# 2-MCU.net
KiCad netlist of a schematic drawn in Altium Designer
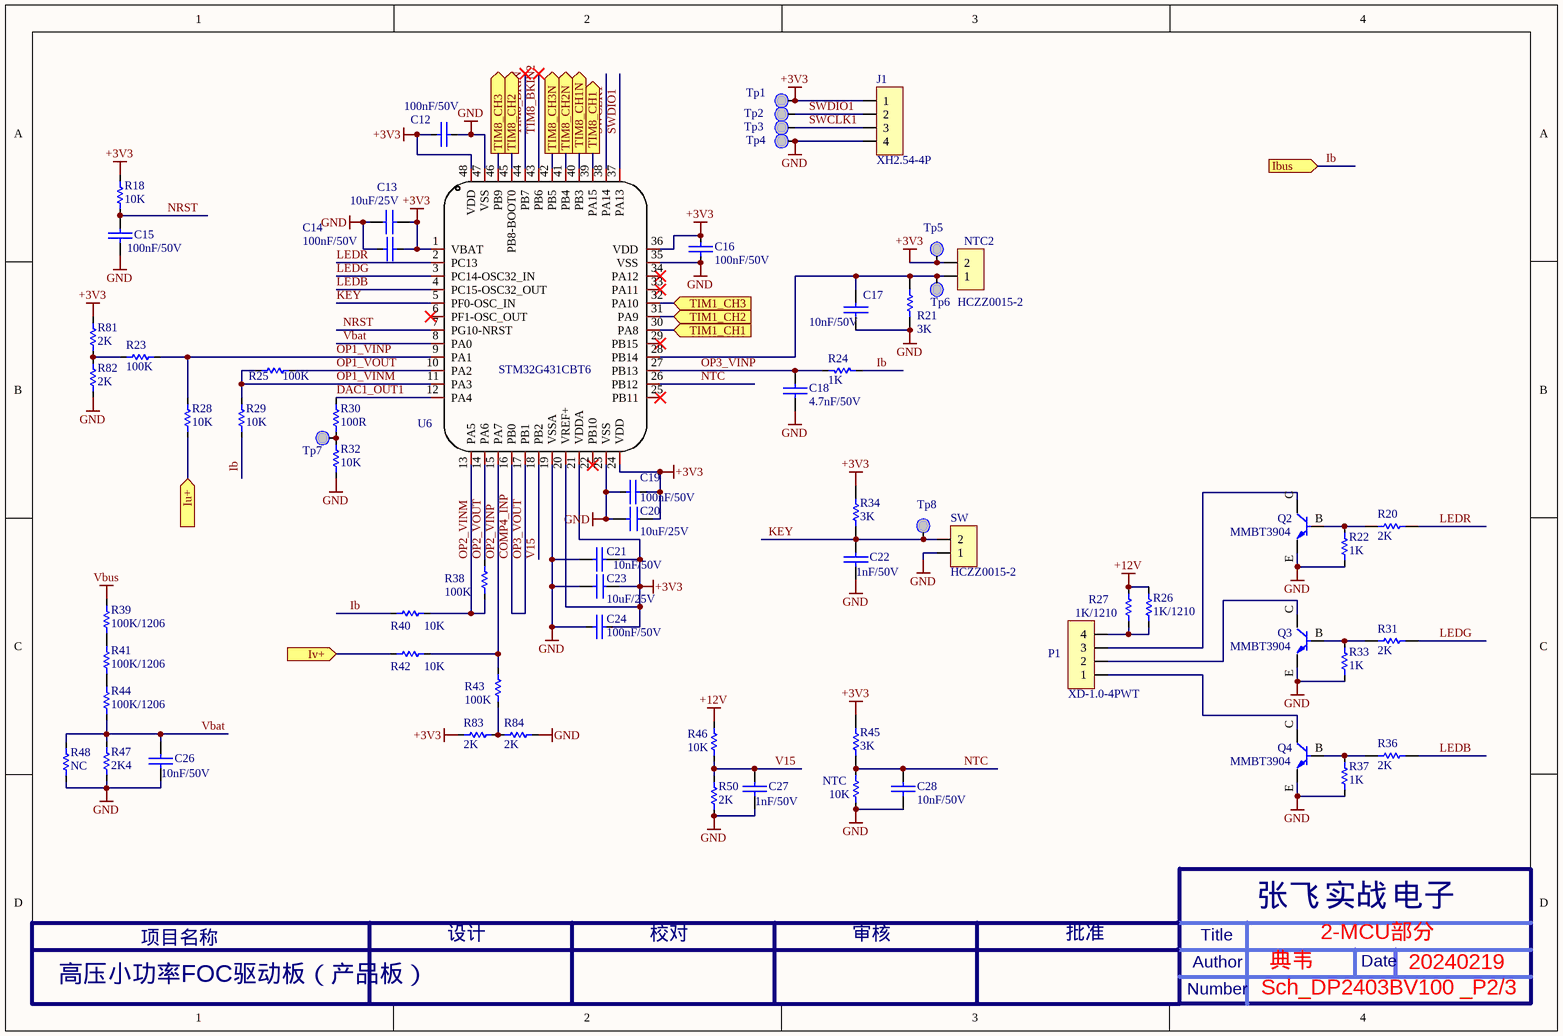
[diagram p0: 2-MCU部分.SchDoc]

(export (version "E")
  (design (tool "Eeschema 10.0.6"))
  (components
    (comp (ref "C12")
      (value "100nF/50V")
      (footprint "C0603")
      (description "贴片电容")
      (libsource (lib "*") (part "CAP NP"))
    )
    (comp (ref "C13")
      (value "10uF/25V")
      (footprint "C0805")
      (description "贴片电容")
      (fields
        (field (name "VOLTAGE") "<Voltage>")
        (field (name "MANUFACTURER") "TDK")
        (field (name "CREATED BY") "JJJ")
      )
      (libsource (lib "*") (part "CAP NP_0"))
    )
    (comp (ref "C14")
      (value "100nF/50V")
      (footprint "C0603")
      (description "贴片电容")
      (libsource (lib "*") (part "CAP NP"))
    )
    (comp (ref "C15")
      (value "100nF/50V")
      (footprint "C0603")
      (description "贴片电容")
      (libsource (lib "*") (part "CAP"))
    )
    (comp (ref "C16")
      (value "100nF/50V")
      (footprint "C0603")
      (description "贴片电容")
      (libsource (lib "*") (part "CAP NP"))
    )
    (comp (ref "C17")
      (value "10nF/50V")
      (footprint "C0603")
      (description "贴片电容")
      (libsource (lib "*") (part "CAP"))
    )
    (comp (ref "C18")
      (value "4.7nF/50V")
      (footprint "C0603")
      (description "贴片电容")
      (libsource (lib "*") (part "CAP"))
    )
    (comp (ref "C19")
      (value "100nF/50V")
      (footprint "C0603")
      (description "贴片电容")
      (libsource (lib "*") (part "CAP NP"))
    )
    (comp (ref "C20")
      (value "10uF/25V")
      (footprint "C0805")
      (description "贴片电容")
      (fields
        (field (name "VOLTAGE") "<Voltage>")
        (field (name "MANUFACTURER") "TDK")
        (field (name "CREATED BY") "JJJ")
      )
      (libsource (lib "*") (part "CAP NP_0"))
    )
    (comp (ref "C21")
      (value "10nF/50V")
      (footprint "C0603")
      (description "贴片电容")
      (libsource (lib "*") (part "CAP"))
    )
    (comp (ref "C22")
      (value "1nF/50V")
      (footprint "C0603")
      (description "贴片电容")
      (libsource (lib "*") (part "CAP"))
    )
    (comp (ref "C23")
      (value "10uF/25V")
      (footprint "C0805")
      (description "贴片电容")
      (fields
        (field (name "VOLTAGE") "<Voltage>")
        (field (name "MANUFACTURER") "TDK")
        (field (name "CREATED BY") "JJJ")
      )
      (libsource (lib "*") (part "CAP NP_0"))
    )
    (comp (ref "C24")
      (value "100nF/50V")
      (footprint "C0603")
      (description "贴片电容")
      (libsource (lib "*") (part "CAP NP"))
    )
    (comp (ref "C26")
      (value "10nF/50V")
      (footprint "C0603")
      (description "贴片电容")
      (libsource (lib "*") (part "CAP"))
    )
    (comp (ref "C27")
      (value "1nF/50V")
      (footprint "C0603")
      (description "贴片电容")
      (libsource (lib "*") (part "CAP"))
    )
    (comp (ref "C28")
      (value "10nF/50V")
      (footprint "C0603")
      (description "贴片电容")
      (libsource (lib "*") (part "CAP"))
    )
    (comp (ref "J1")
      (value "XH2.54-4P")
      (footprint "SIP4")
      (description "接插件")
      (libsource (lib "ZF_SchLib_V0.15") (part "4PIN"))
    )
    (comp (ref "NTC")
      (value "10K")
      (footprint "R0603")
      (description "NTC=10K")
      (fields
        (field (name "MANUFACTURER") "Generic Components")
        (field (name "PUBLISHER") "Altium Hobart Technology Centre")
      )
      (libsource (lib "ZF-V1.00(2022-6-13)") (part "Res"))
    )
    (comp (ref "NTC2")
      (value "HCZZ0015-2")
      (footprint "PIN-2-LS")
      (description "HCZZ0015-2,2P,1.25mm")
      (libsource (lib "ZF-V1.00(2022-6-13)") (part "2PIN"))
    )
    (comp (ref "P1")
      (value "XD-1.0-4PWT")
      (footprint "PIN-4-WS")
      (description "XD-1.0-4PWT,1*4P")
      (libsource (lib "") (part "4PIN_1"))
    )
    (comp (ref "Q2")
      (value "MMBT3904")
      (footprint "SOT-23-BCE")
      (description "三极管")
      (libsource (lib "ZF_SchLib_V0.15") (part "BJT-NPN"))
    )
    (comp (ref "Q3")
      (value "MMBT3904")
      (footprint "SOT-23-BCE")
      (description "三极管")
      (libsource (lib "ZF_SchLib_V0.15") (part "BJT-NPN"))
    )
    (comp (ref "Q4")
      (value "MMBT3904")
      (footprint "SOT-23-BCE")
      (description "三极管")
      (libsource (lib "ZF_SchLib_V0.15") (part "BJT-NPN"))
    )
    (comp (ref "R18")
      (value "10K")
      (footprint "R0603")
      (description "电阻")
      (fields
        (field (name "MANUFACTURER") "Generic Components")
        (field (name "PUBLISHER") "Altium Hobart Technology Centre")
      )
      (libsource (lib "ZF-V1.00(2022-6-13)") (part "Res"))
    )
    (comp (ref "R20")
      (value "2K")
      (footprint "R0603")
      (description "电阻")
      (fields
        (field (name "MANUFACTURER") "Generic Components")
        (field (name "PUBLISHER") "Altium Hobart Technology Centre")
      )
      (libsource (lib "ZF_SchLib_V0.15") (part "Res"))
    )
    (comp (ref "R21")
      (value "3K")
      (footprint "R0603")
      (description "电阻")
      (fields
        (field (name "MANUFACTURER") "Generic Components")
        (field (name "PUBLISHER") "Altium Hobart Technology Centre")
      )
      (libsource (lib "ZF_SchLib_V0.15") (part "Res"))
    )
    (comp (ref "R22")
      (value "1K")
      (footprint "R0603")
      (description "电阻")
      (fields
        (field (name "MANUFACTURER") "Generic Components")
        (field (name "PUBLISHER") "Altium Hobart Technology Centre")
      )
      (libsource (lib "ZF-V1.00(2022-6-13)") (part "Res"))
    )
    (comp (ref "R23")
      (value "100K")
      (footprint "R0603")
      (description "电阻")
      (fields
        (field (name "MANUFACTURER") "Generic Components")
        (field (name "PUBLISHER") "Altium Hobart Technology Centre")
      )
      (libsource (lib "ZF-V1.00(2022-6-13)") (part "Res"))
    )
    (comp (ref "R24")
      (value "1K")
      (footprint "R0603")
      (description "电阻")
      (fields
        (field (name "MANUFACTURER") "Generic Components")
        (field (name "PUBLISHER") "Altium Hobart Technology Centre")
      )
      (libsource (lib "ZF-V1.00(2022-6-13)") (part "Res"))
    )
    (comp (ref "R25")
      (value "100K")
      (footprint "R0603")
      (description "电阻")
      (fields
        (field (name "MANUFACTURER") "Generic Components")
        (field (name "PUBLISHER") "Altium Hobart Technology Centre")
      )
      (libsource (lib "ZF-V1.00(2022-6-13)") (part "Res"))
    )
    (comp (ref "R26")
      (value "1K/1210")
      (footprint "R1210")
      (description "电阻")
      (fields
        (field (name "MANUFACTURER") "Generic Components")
        (field (name "PUBLISHER") "Altium Hobart Technology Centre")
      )
      (libsource (lib "ZF-V1.00(2022-6-13)") (part "Res"))
    )
    (comp (ref "R27")
      (value "1K/1210")
      (footprint "R1210")
      (description "电阻")
      (fields
        (field (name "MANUFACTURER") "Generic Components")
        (field (name "PUBLISHER") "Altium Hobart Technology Centre")
      )
      (libsource (lib "ZF-V1.00(2022-6-13)") (part "Res"))
    )
    (comp (ref "R28")
      (value "10K")
      (footprint "R0603")
      (description "电阻")
      (fields
        (field (name "MANUFACTURER") "Generic Components")
        (field (name "PUBLISHER") "Altium Hobart Technology Centre")
      )
      (libsource (lib "ZF-V1.00(2022-6-13)") (part "Res"))
    )
    (comp (ref "R29")
      (value "10K")
      (footprint "R0603")
      (description "电阻")
      (fields
        (field (name "MANUFACTURER") "Generic Components")
        (field (name "PUBLISHER") "Altium Hobart Technology Centre")
      )
      (libsource (lib "ZF-V1.00(2022-6-13)") (part "Res"))
    )
    (comp (ref "R30")
      (value "100R")
      (footprint "R0603")
      (description "电阻")
      (fields
        (field (name "MANUFACTURER") "Generic Components")
        (field (name "PUBLISHER") "Altium Hobart Technology Centre")
      )
      (libsource (lib "ZF-V1.00(2022-6-13)") (part "Res"))
    )
    (comp (ref "R31")
      (value "2K")
      (footprint "R0603")
      (description "电阻")
      (fields
        (field (name "MANUFACTURER") "Generic Components")
        (field (name "PUBLISHER") "Altium Hobart Technology Centre")
      )
      (libsource (lib "ZF_SchLib_V0.15") (part "Res"))
    )
    (comp (ref "R32")
      (value "10K")
      (footprint "R0603")
      (description "电阻")
      (fields
        (field (name "MANUFACTURER") "Generic Components")
        (field (name "PUBLISHER") "Altium Hobart Technology Centre")
      )
      (libsource (lib "ZF-V1.00(2022-6-13)") (part "Res"))
    )
    (comp (ref "R33")
      (value "1K")
      (footprint "R0603")
      (description "电阻")
      (fields
        (field (name "MANUFACTURER") "Generic Components")
        (field (name "PUBLISHER") "Altium Hobart Technology Centre")
      )
      (libsource (lib "ZF-V1.00(2022-6-13)") (part "Res"))
    )
    (comp (ref "R34")
      (value "3K")
      (footprint "R0603")
      (description "电阻")
      (fields
        (field (name "MANUFACTURER") "Generic Components")
        (field (name "PUBLISHER") "Altium Hobart Technology Centre")
      )
      (libsource (lib "ZF_SchLib_V0.15") (part "Res"))
    )
    (comp (ref "R36")
      (value "2K")
      (footprint "R0603")
      (description "电阻")
      (fields
        (field (name "MANUFACTURER") "Generic Components")
        (field (name "PUBLISHER") "Altium Hobart Technology Centre")
      )
      (libsource (lib "ZF_SchLib_V0.15") (part "Res"))
    )
    (comp (ref "R37")
      (value "1K")
      (footprint "R0603")
      (description "电阻")
      (fields
        (field (name "MANUFACTURER") "Generic Components")
        (field (name "PUBLISHER") "Altium Hobart Technology Centre")
      )
      (libsource (lib "ZF-V1.00(2022-6-13)") (part "Res"))
    )
    (comp (ref "R38")
      (value "100K")
      (footprint "R0603")
      (description "电阻")
      (fields
        (field (name "MANUFACTURER") "Generic Components")
        (field (name "PUBLISHER") "Altium Hobart Technology Centre")
      )
      (libsource (lib "ZF-V1.00(2022-6-13)") (part "Res"))
    )
    (comp (ref "R39")
      (value "100K/1206")
      (footprint "R1206")
      (description "电阻")
      (fields
        (field (name "MANUFACTURER") "Generic Components")
        (field (name "PUBLISHER") "Altium Hobart Technology Centre")
      )
      (libsource (lib "ZF-V1.00(2022-6-13)") (part "Res"))
    )
    (comp (ref "R40")
      (value "10K")
      (footprint "R0603")
      (description "电阻")
      (fields
        (field (name "MANUFACTURER") "Generic Components")
        (field (name "PUBLISHER") "Altium Hobart Technology Centre")
      )
      (libsource (lib "ZF-V1.00(2022-6-13)") (part "Res"))
    )
    (comp (ref "R41")
      (value "100K/1206")
      (footprint "R1206")
      (description "电阻")
      (fields
        (field (name "MANUFACTURER") "Generic Components")
        (field (name "PUBLISHER") "Altium Hobart Technology Centre")
      )
      (libsource (lib "ZF-V1.00(2022-6-13)") (part "Res"))
    )
    (comp (ref "R42")
      (value "10K")
      (footprint "R0603")
      (description "电阻")
      (fields
        (field (name "MANUFACTURER") "Generic Components")
        (field (name "PUBLISHER") "Altium Hobart Technology Centre")
      )
      (libsource (lib "ZF-V1.00(2022-6-13)") (part "Res"))
    )
    (comp (ref "R43")
      (value "100K")
      (footprint "R0603")
      (description "电阻")
      (fields
        (field (name "MANUFACTURER") "Generic Components")
        (field (name "PUBLISHER") "Altium Hobart Technology Centre")
      )
      (libsource (lib "ZF-V1.00(2022-6-13)") (part "Res"))
    )
    (comp (ref "R44")
      (value "100K/1206")
      (footprint "R1206")
      (description "电阻")
      (fields
        (field (name "MANUFACTURER") "Generic Components")
        (field (name "PUBLISHER") "Altium Hobart Technology Centre")
      )
      (libsource (lib "ZF-V1.00(2022-6-13)") (part "Res"))
    )
    (comp (ref "R45")
      (value "3K")
      (footprint "R0603")
      (description "电阻")
      (fields
        (field (name "MANUFACTURER") "Generic Components")
        (field (name "PUBLISHER") "Altium Hobart Technology Centre")
      )
      (libsource (lib "ZF_SchLib_V0.15") (part "Res"))
    )
    (comp (ref "R46")
      (value "10K")
      (footprint "R0603")
      (description "电阻")
      (fields
        (field (name "MANUFACTURER") "Generic Components")
        (field (name "PUBLISHER") "Altium Hobart Technology Centre")
      )
      (libsource (lib "ZF-V1.00(2022-6-13)") (part "Res"))
    )
    (comp (ref "R47")
      (value "2K4")
      (footprint "R0603")
      (description "电阻")
      (fields
        (field (name "MANUFACTURER") "Generic Components")
        (field (name "PUBLISHER") "Altium Hobart Technology Centre")
      )
      (libsource (lib "ZF-V1.00(2022-6-13)") (part "Res"))
    )
    (comp (ref "R48")
      (value "NC")
      (footprint "R0603")
      (description "电阻")
      (fields
        (field (name "MANUFACTURER") "Generic Components")
        (field (name "PUBLISHER") "Altium Hobart Technology Centre")
      )
      (libsource (lib "ZF-V1.00(2022-6-13)") (part "Res"))
    )
    (comp (ref "R50")
      (value "2K")
      (footprint "R0603")
      (description "电阻")
      (fields
        (field (name "MANUFACTURER") "Generic Components")
        (field (name "PUBLISHER") "Altium Hobart Technology Centre")
      )
      (libsource (lib "ZF-V1.00(2022-6-13)") (part "Res"))
    )
    (comp (ref "R81")
      (value "2K")
      (footprint "R0603")
      (description "电阻")
      (fields
        (field (name "MANUFACTURER") "Generic Components")
        (field (name "PUBLISHER") "Altium Hobart Technology Centre")
      )
      (libsource (lib "ZF-V1.00(2022-6-13)") (part "Res"))
    )
    (comp (ref "R82")
      (value "2K")
      (footprint "R0603")
      (description "电阻")
      (fields
        (field (name "MANUFACTURER") "Generic Components")
        (field (name "PUBLISHER") "Altium Hobart Technology Centre")
      )
      (libsource (lib "ZF-V1.00(2022-6-13)") (part "Res"))
    )
    (comp (ref "R83")
      (value "2K")
      (footprint "R0603")
      (description "电阻")
      (fields
        (field (name "MANUFACTURER") "Generic Components")
        (field (name "PUBLISHER") "Altium Hobart Technology Centre")
      )
      (libsource (lib "ZF-V1.00(2022-6-13)") (part "Res"))
    )
    (comp (ref "R84")
      (value "2K")
      (footprint "R0603")
      (description "电阻")
      (fields
        (field (name "MANUFACTURER") "Generic Components")
        (field (name "PUBLISHER") "Altium Hobart Technology Centre")
      )
      (libsource (lib "ZF-V1.00(2022-6-13)") (part "Res"))
    )
    (comp (ref "SW")
      (value "HCZZ0015-2")
      (footprint "PIN-2-LS")
      (description "HCZZ0015-2,2P,1.25mm")
      (libsource (lib "ZF-V1.00(2022-6-13)") (part "2PIN"))
    )
    (comp (ref "Tp1")
      (value "test point")
      (footprint "Test_Port")
      (libsource (lib "RUKING-Passive Component Schematic library V01") (part "test point"))
    )
    (comp (ref "Tp2")
      (value "test point")
      (footprint "Test_Port")
      (libsource (lib "RUKING-Passive Component Schematic library V01") (part "test point"))
    )
    (comp (ref "Tp3")
      (value "test point")
      (footprint "Test_Port")
      (libsource (lib "RUKING-Passive Component Schematic library V01") (part "test point"))
    )
    (comp (ref "Tp4")
      (value "test point")
      (footprint "Test_Port")
      (libsource (lib "RUKING-Passive Component Schematic library V01") (part "test point"))
    )
    (comp (ref "Tp5") (value "test point") (footprint "Test_Port") (libsource (lib "") (part "test point_1")))
    (comp (ref "Tp6") (value "test point") (footprint "Test_Port") (libsource (lib "") (part "test point_2")))
    (comp (ref "Tp7")
      (value "test point")
      (footprint "Test_Port")
      (libsource (lib "RUKING-Passive Component Schematic library V01") (part "test point"))
    )
    (comp (ref "Tp8") (value "test point") (footprint "Test_Port") (libsource (lib "") (part "test point_1")))
    (comp (ref "U6")
      (value "STM32G431CBT6")
      (footprint "LQFP-48")
      (fields (field (name "MANUFACTURER") "ST(意法半导体)"))
      (libsource (lib "altium-import") (part "root_0_STM32G431CBT6_"))
    )
  )
  (nets
    (net (code "1") (name "+3V3") (class "Default")
      (node (ref "C12") (pin "2") (pinfunction "2_2") (pintype "passive"))
      (node (ref "C13") (pin "2") (pinfunction "2_2") (pintype "passive"))
      (node (ref "C14") (pin "1") (pinfunction "1_1") (pintype "passive"))
      (node (ref "C16") (pin "2") (pinfunction "2_2") (pintype "passive"))
      (node (ref "C19") (pin "2") (pinfunction "2_2") (pintype "passive"))
      (node (ref "C20") (pin "1") (pinfunction "1_1") (pintype "passive"))
      (node (ref "C21") (pin "2") (pinfunction "2_2") (pintype "passive"))
      (node (ref "C23") (pin "1") (pinfunction "1_1") (pintype "passive"))
      (node (ref "C24") (pin "2") (pinfunction "2_2") (pintype "passive"))
      (node (ref "J1") (pin "1") (pinfunction "1_1") (pintype "passive"))
      (node (ref "NTC2") (pin "2") (pinfunction "2_2") (pintype "passive"))
      (node (ref "R18") (pin "1") (pinfunction "1_1") (pintype "passive"))
      (node (ref "R34") (pin "1") (pinfunction "1_1") (pintype "passive"))
      (node (ref "R45") (pin "1") (pinfunction "1_1") (pintype "passive"))
      (node (ref "R81") (pin "1") (pinfunction "1_1") (pintype "passive"))
      (node (ref "R83") (pin "1") (pinfunction "1_1") (pintype "passive"))
      (node (ref "Tp1") (pin "1") (pinfunction "Test_1") (pintype "passive"))
      (node (ref "Tp5") (pin "1") (pinfunction "Test_1") (pintype "passive"))
      (node (ref "U6") (pin "1") (pinfunction "VBAT_1") (pintype "passive"))
      (node (ref "U6") (pin "20") (pinfunction "VREF+_20") (pintype "passive"))
      (node (ref "U6") (pin "21") (pinfunction "VDDA_21") (pintype "passive"))
      (node (ref "U6") (pin "24") (pinfunction "VDD_24") (pintype "passive"))
      (node (ref "U6") (pin "36") (pinfunction "VDD_36") (pintype "passive"))
      (node (ref "U6") (pin "48") (pinfunction "VDD_48") (pintype "passive"))
    )
    (net (code "2") (name "+12V") (class "Default")
      (node (ref "R26") (pin "1") (pinfunction "1_1") (pintype "passive"))
      (node (ref "R27") (pin "1") (pinfunction "1_1") (pintype "passive"))
      (node (ref "R46") (pin "1") (pinfunction "1_1") (pintype "passive"))
    )
    (net (code "3") (name "/COMP4_INP") (class "Default")
      (node (ref "U6") (pin "16") (pinfunction "PB0_16") (pintype "passive"))
      (node (ref "U6") (pin "17") (pinfunction "PB1_17") (pintype "passive"))
    )
    (net (code "4") (name "/DAC1_OUT1") (class "Default")
      (node (ref "R30") (pin "1") (pinfunction "1_1") (pintype "passive"))
      (node (ref "U6") (pin "12") (pinfunction "PA4_12") (pintype "passive"))
    )
    (net (code "5") (name "/Ib") (class "Default")
      (node (ref "R24") (pin "2") (pinfunction "2_2") (pintype "passive"))
      (node (ref "R29") (pin "1") (pinfunction "1_1") (pintype "passive"))
      (node (ref "R40") (pin "2") (pinfunction "2_2") (pintype "passive"))
    )
    (net (code "6") (name "/Iu+") (class "Default")
      (node (ref "R28") (pin "2") (pinfunction "2_2") (pintype "passive"))
    )
    (net (code "7") (name "/Iv+") (class "Default")
      (node (ref "R42") (pin "1") (pinfunction "1_1") (pintype "passive"))
    )
    (net (code "8") (name "/KEY") (class "Default")
      (node (ref "C22") (pin "1") (pinfunction "1_1") (pintype "passive"))
      (node (ref "R34") (pin "2") (pinfunction "2_2") (pintype "passive"))
      (node (ref "SW") (pin "2") (pinfunction "2_2") (pintype "passive"))
      (node (ref "Tp8") (pin "1") (pinfunction "Test_1") (pintype "passive"))
      (node (ref "U6") (pin "5") (pinfunction "PF0-OSC_IN_5") (pintype "passive"))
    )
    (net (code "9") (name "/LEDB") (class "Default")
      (node (ref "R36") (pin "2") (pinfunction "2_2") (pintype "passive"))
      (node (ref "U6") (pin "4") (pinfunction "PC15-OSC32_OUT_4") (pintype "passive"))
    )
    (net (code "10") (name "/LEDG") (class "Default")
      (node (ref "R31") (pin "2") (pinfunction "2_2") (pintype "passive"))
      (node (ref "U6") (pin "3") (pinfunction "PC14-OSC32_IN_3") (pintype "passive"))
    )
    (net (code "11") (name "/LEDR") (class "Default")
      (node (ref "R20") (pin "2") (pinfunction "2_2") (pintype "passive"))
      (node (ref "U6") (pin "2") (pinfunction "PC13_2") (pintype "passive"))
    )
    (net (code "12") (name "/NRST") (class "Default")
      (node (ref "C15") (pin "1") (pinfunction "1_1") (pintype "passive"))
      (node (ref "R18") (pin "2") (pinfunction "2_2") (pintype "passive"))
      (node (ref "U6") (pin "7") (pinfunction "PG10-NRST_7") (pintype "passive"))
    )
    (net (code "13") (name "/NTC") (class "Default")
      (node (ref "C28") (pin "2") (pinfunction "2_2") (pintype "passive"))
      (node (ref "NTC") (pin "1") (pinfunction "1_1") (pintype "passive"))
      (node (ref "R45") (pin "2") (pinfunction "2_2") (pintype "passive"))
      (node (ref "U6") (pin "26") (pinfunction "PB12_26") (pintype "passive"))
    )
    (net (code "14") (name "/OP1_VINM") (class "Default")
      (node (ref "R25") (pin "1") (pinfunction "1_1") (pintype "passive"))
      (node (ref "R29") (pin "2") (pinfunction "2_2") (pintype "passive"))
      (node (ref "U6") (pin "11") (pinfunction "PA3_11") (pintype "passive"))
    )
    (net (code "15") (name "/OP1_VINP") (class "Default")
      (node (ref "R23") (pin "1") (pinfunction "1_1") (pintype "passive"))
      (node (ref "R28") (pin "1") (pinfunction "1_1") (pintype "passive"))
      (node (ref "U6") (pin "9") (pinfunction "PA1_9") (pintype "passive"))
    )
    (net (code "16") (name "/OP1_VOUT") (class "Default")
      (node (ref "R25") (pin "2") (pinfunction "2_2") (pintype "passive"))
      (node (ref "U6") (pin "10") (pinfunction "PA2_10") (pintype "passive"))
    )
    (net (code "17") (name "/OP2_VINM") (class "Default")
      (node (ref "R38") (pin "1") (pinfunction "1_1") (pintype "passive"))
      (node (ref "R40") (pin "1") (pinfunction "1_1") (pintype "passive"))
      (node (ref "U6") (pin "13") (pinfunction "PA5_13") (pintype "passive"))
    )
    (net (code "18") (name "/OP2_VINP") (class "Default")
      (node (ref "R42") (pin "2") (pinfunction "2_2") (pintype "passive"))
      (node (ref "R43") (pin "1") (pinfunction "1_1") (pintype "passive"))
      (node (ref "U6") (pin "15") (pinfunction "PA7_15") (pintype "passive"))
    )
    (net (code "19") (name "/OP2_VOUT") (class "Default")
      (node (ref "R38") (pin "2") (pinfunction "2_2") (pintype "passive"))
      (node (ref "U6") (pin "14") (pinfunction "PA6_14") (pintype "passive"))
    )
    (net (code "20") (name "/OP3_VINP") (class "Default")
      (node (ref "C18") (pin "1") (pinfunction "1_1") (pintype "passive"))
      (node (ref "R24") (pin "1") (pinfunction "1_1") (pintype "passive"))
      (node (ref "U6") (pin "27") (pinfunction "PB13_27") (pintype "passive"))
    )
    (net (code "21") (name "/SWCLK1") (class "Default")
      (node (ref "J1") (pin "3") (pinfunction "3_3") (pintype "passive"))
      (node (ref "Tp3") (pin "1") (pinfunction "Test_1") (pintype "passive"))
      (node (ref "U6") (pin "38") (pinfunction "PA14_38") (pintype "passive"))
    )
    (net (code "22") (name "/SWDIO1") (class "Default")
      (node (ref "J1") (pin "2") (pinfunction "2_2") (pintype "passive"))
      (node (ref "Tp2") (pin "1") (pinfunction "Test_1") (pintype "passive"))
      (node (ref "U6") (pin "37") (pinfunction "PA13_37") (pintype "passive"))
    )
    (net (code "23") (name "/TIM1_CH1") (class "Default")
      (node (ref "U6") (pin "30") (pinfunction "PA8_30") (pintype "passive"))
    )
    (net (code "24") (name "/TIM1_CH2") (class "Default")
      (node (ref "U6") (pin "31") (pinfunction "PA9_31") (pintype "passive"))
    )
    (net (code "25") (name "/TIM1_CH3") (class "Default")
      (node (ref "U6") (pin "32") (pinfunction "PA10_32") (pintype "passive"))
    )
    (net (code "26") (name "/TIM8_BKIN") (class "Default")
      (node (ref "U6") (pin "44") (pinfunction "PB7_44") (pintype "passive+no_connect"))
    )
    (net (code "27") (name "/TIM8_BKIN2") (class "Default")
      (node (ref "U6") (pin "43") (pinfunction "PB6_43") (pintype "passive+no_connect"))
    )
    (net (code "28") (name "/TIM8_CH1") (class "Default")
      (node (ref "U6") (pin "39") (pinfunction "PA15_39") (pintype "passive"))
    )
    (net (code "29") (name "/TIM8_CH1N") (class "Default")
      (node (ref "U6") (pin "40") (pinfunction "PB3_40") (pintype "passive"))
    )
    (net (code "30") (name "/TIM8_CH2") (class "Default")
      (node (ref "U6") (pin "45") (pinfunction "PB8-BOOT0_45") (pintype "passive"))
    )
    (net (code "31") (name "/TIM8_CH2N") (class "Default")
      (node (ref "U6") (pin "41") (pinfunction "PB4_41") (pintype "passive"))
    )
    (net (code "32") (name "/TIM8_CH3") (class "Default")
      (node (ref "U6") (pin "46") (pinfunction "PB9_46") (pintype "passive"))
    )
    (net (code "33") (name "/TIM8_CH3N") (class "Default")
      (node (ref "U6") (pin "42") (pinfunction "PB5_42") (pintype "passive"))
    )
    (net (code "34") (name "/V15") (class "Default")
      (node (ref "C27") (pin "1") (pinfunction "1_1") (pintype "passive"))
      (node (ref "R46") (pin "2") (pinfunction "2_2") (pintype "passive"))
      (node (ref "R50") (pin "2") (pinfunction "2_2") (pintype "passive"))
      (node (ref "U6") (pin "18") (pinfunction "PB2_18") (pintype "passive"))
    )
    (net (code "35") (name "/Vbat") (class "Default")
      (node (ref "C26") (pin "1") (pinfunction "1_1") (pintype "passive"))
      (node (ref "R44") (pin "2") (pinfunction "2_2") (pintype "passive"))
      (node (ref "R47") (pin "2") (pinfunction "2_2") (pintype "passive"))
      (node (ref "R48") (pin "2") (pinfunction "2_2") (pintype "passive"))
      (node (ref "U6") (pin "8") (pinfunction "PA0_8") (pintype "passive"))
    )
    (net (code "36") (name "GND") (class "Default")
      (node (ref "C12") (pin "1") (pinfunction "1_1") (pintype "passive"))
      (node (ref "C13") (pin "1") (pinfunction "1_1") (pintype "passive"))
      (node (ref "C14") (pin "2") (pinfunction "2_2") (pintype "passive"))
      (node (ref "C15") (pin "2") (pinfunction "2_2") (pintype "passive"))
      (node (ref "C16") (pin "1") (pinfunction "1_1") (pintype "passive"))
      (node (ref "C17") (pin "1") (pinfunction "1_1") (pintype "passive"))
      (node (ref "C18") (pin "2") (pinfunction "2_2") (pintype "passive"))
      (node (ref "C19") (pin "1") (pinfunction "1_1") (pintype "passive"))
      (node (ref "C20") (pin "2") (pinfunction "2_2") (pintype "passive"))
      (node (ref "C21") (pin "1") (pinfunction "1_1") (pintype "passive"))
      (node (ref "C22") (pin "2") (pinfunction "2_2") (pintype "passive"))
      (node (ref "C23") (pin "2") (pinfunction "2_2") (pintype "passive"))
      (node (ref "C24") (pin "1") (pinfunction "1_1") (pintype "passive"))
      (node (ref "C26") (pin "2") (pinfunction "2_2") (pintype "passive"))
      (node (ref "C27") (pin "2") (pinfunction "2_2") (pintype "passive"))
      (node (ref "C28") (pin "1") (pinfunction "1_1") (pintype "passive"))
      (node (ref "J1") (pin "4") (pinfunction "4_4") (pintype "passive"))
      (node (ref "NTC") (pin "2") (pinfunction "2_2") (pintype "passive"))
      (node (ref "Q2") (pin "E") (pinfunction "2_E") (pintype "passive"))
      (node (ref "Q3") (pin "E") (pinfunction "2_E") (pintype "passive"))
      (node (ref "Q4") (pin "E") (pinfunction "2_E") (pintype "passive"))
      (node (ref "R21") (pin "2") (pinfunction "2_2") (pintype "passive"))
      (node (ref "R22") (pin "2") (pinfunction "2_2") (pintype "passive"))
      (node (ref "R32") (pin "1") (pinfunction "1_1") (pintype "passive"))
      (node (ref "R33") (pin "2") (pinfunction "2_2") (pintype "passive"))
      (node (ref "R37") (pin "2") (pinfunction "2_2") (pintype "passive"))
      (node (ref "R47") (pin "1") (pinfunction "1_1") (pintype "passive"))
      (node (ref "R48") (pin "1") (pinfunction "1_1") (pintype "passive"))
      (node (ref "R50") (pin "1") (pinfunction "1_1") (pintype "passive"))
      (node (ref "R82") (pin "2") (pinfunction "2_2") (pintype "passive"))
      (node (ref "R84") (pin "2") (pinfunction "2_2") (pintype "passive"))
      (node (ref "SW") (pin "1") (pinfunction "1_1") (pintype "passive"))
      (node (ref "Tp4") (pin "1") (pinfunction "Test_1") (pintype "passive"))
      (node (ref "U6") (pin "19") (pinfunction "VSSA_19") (pintype "passive"))
      (node (ref "U6") (pin "23") (pinfunction "VSS_23") (pintype "passive"))
      (node (ref "U6") (pin "35") (pinfunction "VSS_35") (pintype "passive"))
      (node (ref "U6") (pin "47") (pinfunction "VSS_47") (pintype "passive"))
    )
    (net (code "37") (name "Net-(P1-Pad4)") (class "Default")
      (node (ref "P1") (pin "4") (pinfunction "4_4") (pintype "passive"))
      (node (ref "R26") (pin "2") (pinfunction "2_2") (pintype "passive"))
      (node (ref "R27") (pin "2") (pinfunction "2_2") (pintype "passive"))
    )
    (net (code "38") (name "Net-(Q2-1)") (class "Default")
      (node (ref "Q2") (pin "B") (pinfunction "1_B") (pintype "passive"))
      (node (ref "R20") (pin "1") (pinfunction "1_1") (pintype "passive"))
      (node (ref "R22") (pin "1") (pinfunction "1_1") (pintype "passive"))
    )
    (net (code "39") (name "Net-(Q2-3)") (class "Default")
      (node (ref "P1") (pin "3") (pinfunction "3_3") (pintype "passive"))
      (node (ref "Q2") (pin "C") (pinfunction "3_C") (pintype "passive"))
    )
    (net (code "40") (name "Net-(Q3-1)") (class "Default")
      (node (ref "Q3") (pin "B") (pinfunction "1_B") (pintype "passive"))
      (node (ref "R31") (pin "1") (pinfunction "1_1") (pintype "passive"))
      (node (ref "R33") (pin "1") (pinfunction "1_1") (pintype "passive"))
    )
    (net (code "41") (name "Net-(Q3-3)") (class "Default")
      (node (ref "P1") (pin "2") (pinfunction "2_2") (pintype "passive"))
      (node (ref "Q3") (pin "C") (pinfunction "3_C") (pintype "passive"))
    )
    (net (code "42") (name "Net-(Q4-1)") (class "Default")
      (node (ref "Q4") (pin "B") (pinfunction "1_B") (pintype "passive"))
      (node (ref "R36") (pin "1") (pinfunction "1_1") (pintype "passive"))
      (node (ref "R37") (pin "1") (pinfunction "1_1") (pintype "passive"))
    )
    (net (code "43") (name "Net-(Q4-3)") (class "Default")
      (node (ref "P1") (pin "1") (pinfunction "1_1") (pintype "passive"))
      (node (ref "Q4") (pin "C") (pinfunction "3_C") (pintype "passive"))
    )
    (net (code "44") (name "Net-(R23-Pad2)") (class "Default")
      (node (ref "R23") (pin "2") (pinfunction "2_2") (pintype "passive"))
      (node (ref "R81") (pin "2") (pinfunction "2_2") (pintype "passive"))
      (node (ref "R82") (pin "1") (pinfunction "1_1") (pintype "passive"))
    )
    (net (code "45") (name "Net-(R39-Pad2)") (class "Default")
      (node (ref "R39") (pin "2") (pinfunction "2_2") (pintype "passive"))
      (node (ref "R41") (pin "1") (pinfunction "1_1") (pintype "passive"))
    )
    (net (code "46") (name "Net-(R41-Pad2)") (class "Default")
      (node (ref "R41") (pin "2") (pinfunction "2_2") (pintype "passive"))
      (node (ref "R44") (pin "1") (pinfunction "1_1") (pintype "passive"))
    )
    (net (code "47") (name "Net-(R43-Pad2)") (class "Default")
      (node (ref "R43") (pin "2") (pinfunction "2_2") (pintype "passive"))
      (node (ref "R83") (pin "2") (pinfunction "2_2") (pintype "passive"))
      (node (ref "R84") (pin "1") (pinfunction "1_1") (pintype "passive"))
    )
    (net (code "48") (name "Net-(Tp6-Test)") (class "Default")
      (node (ref "C17") (pin "2") (pinfunction "2_2") (pintype "passive"))
      (node (ref "NTC2") (pin "1") (pinfunction "1_1") (pintype "passive"))
      (node (ref "R21") (pin "1") (pinfunction "1_1") (pintype "passive"))
      (node (ref "Tp6") (pin "1") (pinfunction "Test_1") (pintype "passive"))
      (node (ref "U6") (pin "28") (pinfunction "PB14_28") (pintype "passive"))
    )
    (net (code "49") (name "Net-(Tp7-Test)") (class "Default")
      (node (ref "R30") (pin "2") (pinfunction "2_2") (pintype "passive"))
      (node (ref "R32") (pin "2") (pinfunction "2_2") (pintype "passive"))
      (node (ref "Tp7") (pin "1") (pinfunction "Test_1") (pintype "passive"))
    )
    (net (code "50") (name "Vbus") (class "Default")
      (node (ref "R39") (pin "1") (pinfunction "1_1") (pintype "passive"))
    )
    (net (code "51") (name "unconnected-(U6-PA11-Pad33)") (class "Default")
      (node (ref "U6") (pin "33") (pinfunction "PA11_33") (pintype "passive+no_connect"))
    )
    (net (code "52") (name "unconnected-(U6-PA12-Pad34)") (class "Default")
      (node (ref "U6") (pin "34") (pinfunction "PA12_34") (pintype "passive+no_connect"))
    )
    (net (code "53") (name "unconnected-(U6-PB10-Pad22)") (class "Default")
      (node (ref "U6") (pin "22") (pinfunction "PB10_22") (pintype "passive+no_connect"))
    )
    (net (code "54") (name "unconnected-(U6-PB11-Pad25)") (class "Default")
      (node (ref "U6") (pin "25") (pinfunction "PB11_25") (pintype "passive+no_connect"))
    )
    (net (code "55") (name "unconnected-(U6-PB15-Pad29)") (class "Default")
      (node (ref "U6") (pin "29") (pinfunction "PB15_29") (pintype "passive+no_connect"))
    )
    (net (code "56") (name "unconnected-(U6-PF1-OSC_OUT-Pad6)") (class "Default")
      (node (ref "U6") (pin "6") (pinfunction "PF1-OSC_OUT_6") (pintype "passive+no_connect"))
    )
  )
)
